# SCH_AGV_genzero_main_board_2024-06-24.net
KiCad netlist of a schematic drawn in EasyEDA
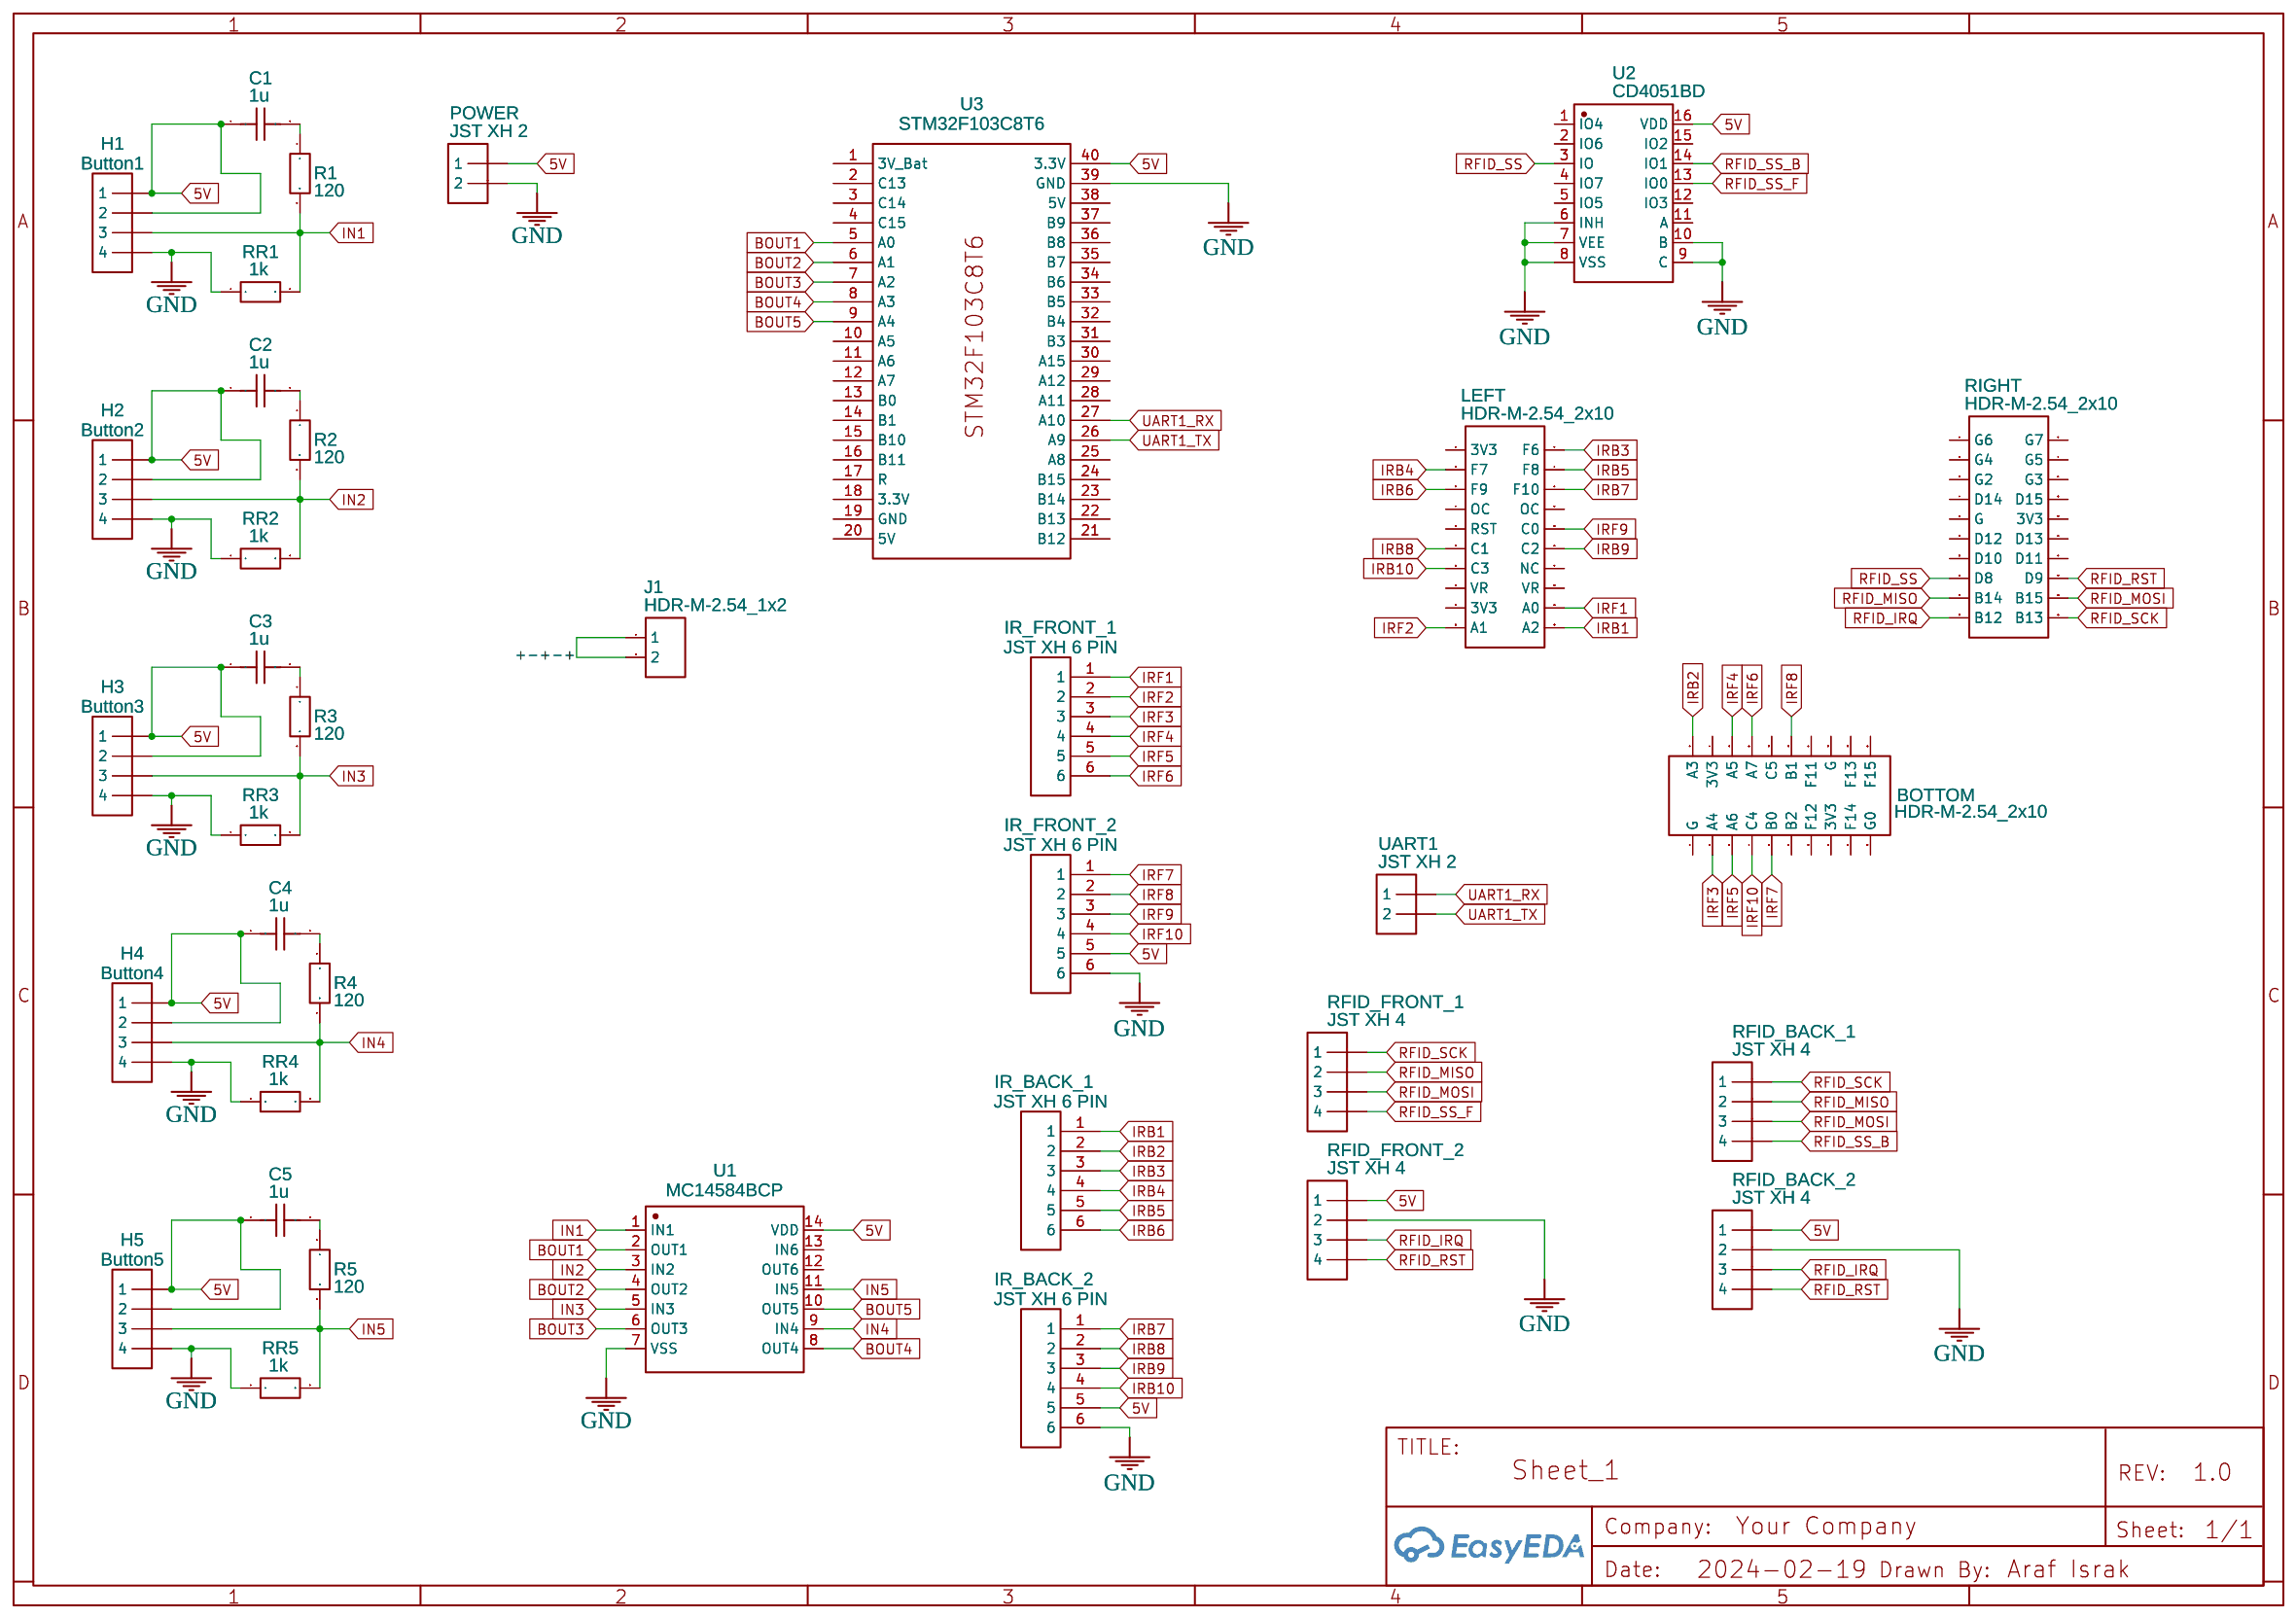
[diagram p0: schematic sheet]

(export (version "E")
  (design (tool "Eeschema 10.0.6"))
  (components
    (comp (ref "BOTTOM") (value "HDR-M-2.54_2x10") (libsource (lib "") (part "HDR-M-2.54_2x10_2")))
    (comp (ref "C1") (value "1u") (libsource (lib "") (part "C_RAD-0.1_US")))
    (comp (ref "C2") (value "1u") (libsource (lib "") (part "C_RAD-0.1_US")))
    (comp (ref "C3") (value "1u") (libsource (lib "") (part "C_RAD-0.1_US")))
    (comp (ref "C4") (value "1u") (libsource (lib "") (part "C_RAD-0.1_US")))
    (comp (ref "C5") (value "1u") (libsource (lib "") (part "C_RAD-0.1_US")))
    (comp (ref "H1") (value "Button1") (libsource (lib "") (part "JST XH 4_1")))
    (comp (ref "H2") (value "Button2") (libsource (lib "") (part "JST XH 4_1")))
    (comp (ref "H3") (value "Button3") (libsource (lib "") (part "JST XH 4_1")))
    (comp (ref "H4") (value "Button4") (libsource (lib "") (part "JST XH 4_1")))
    (comp (ref "H5") (value "Button5") (libsource (lib "") (part "JST XH 4_1")))
    (comp (ref "IR_BACK_1") (value "JST XH 6 PIN") (libsource (lib "") (part "JST XH 6 PIN")))
    (comp (ref "IR_BACK_2") (value "JST XH 6 PIN") (libsource (lib "") (part "JST XH 6 PIN")))
    (comp (ref "IR_FRONT_1") (value "JST XH 6 PIN") (libsource (lib "") (part "JST XH 6 PIN_1")))
    (comp (ref "IR_FRONT_2") (value "JST XH 6 PIN") (libsource (lib "") (part "JST XH 6 PIN_1")))
    (comp (ref "J1") (value "HDR-M-2.54_1x2") (libsource (lib "") (part "HDR-M-2.54_1x2")))
    (comp (ref "LEFT") (value "HDR-M-2.54_2x10") (libsource (lib "") (part "HDR-M-2.54_2x10")))
    (comp (ref "POWER") (value "JST XH 2") (libsource (lib "") (part "JST XH 2_1")))
    (comp (ref "R1") (value "120") (libsource (lib "") (part "R_AXIAL-0.4_EU_1")))
    (comp (ref "R2") (value "120") (libsource (lib "") (part "R_AXIAL-0.4_EU_1")))
    (comp (ref "R3") (value "120") (libsource (lib "") (part "R_AXIAL-0.4_EU_1")))
    (comp (ref "R4") (value "120") (libsource (lib "") (part "R_AXIAL-0.4_EU_1")))
    (comp (ref "R5") (value "120") (libsource (lib "") (part "R_AXIAL-0.4_EU_1")))
    (comp (ref "RFID_BACK_1") (value "JST XH 4") (libsource (lib "") (part "JST XH 4")))
    (comp (ref "RFID_BACK_2") (value "JST XH 4") (libsource (lib "") (part "JST XH 4")))
    (comp (ref "RFID_FRONT_1") (value "JST XH 4") (libsource (lib "") (part "JST XH 4_2")))
    (comp (ref "RFID_FRONT_2") (value "JST XH 4") (libsource (lib "") (part "JST XH 4_2")))
    (comp (ref "RIGHT") (value "HDR-M-2.54_2x10") (libsource (lib "") (part "HDR-M-2.54_2x10_1")))
    (comp (ref "RR1") (value "1k") (libsource (lib "") (part "R_AXIAL-0.4_EU")))
    (comp (ref "RR2") (value "1k") (libsource (lib "") (part "R_AXIAL-0.4_EU")))
    (comp (ref "RR3") (value "1k") (libsource (lib "") (part "R_AXIAL-0.4_EU")))
    (comp (ref "RR4") (value "1k") (libsource (lib "") (part "R_AXIAL-0.4_EU")))
    (comp (ref "RR5") (value "1k") (libsource (lib "") (part "R_AXIAL-0.4_EU")))
    (comp (ref "U1")
      (value "MC14584BCP")
      (fields (field (name "Manufacturer") "ON"))
      (libsource (lib "") (part "MC14584BCP"))
    )
    (comp (ref "U2")
      (value "CD4051BD")
      (fields (field (name "Manufacturer Part") "CD4051BF3A") (field (name "Manufacturer") "TI(德州仪器)"))
      (libsource (lib "") (part "CD4051BD"))
    )
    (comp (ref "U3") (value "STM32F103C8T6") (libsource (lib "") (part "STM32F103C8T6")))
    (comp (ref "UART1") (value "JST XH 2") (libsource (lib "") (part "JST XH 2")))
  )
  (nets
    (net (code "1") (name "/+-+-+") (class "Default")
      (node (ref "J1") (pin "1") (pinfunction "1_1") (pintype "unspecified"))
      (node (ref "J1") (pin "2") (pinfunction "2_2") (pintype "unspecified"))
    )
    (net (code "2") (name "5V") (class "Default")
      (node (ref "C1") (pin "1") (pinfunction "1_1") (pintype "unspecified"))
      (node (ref "C2") (pin "1") (pinfunction "1_1") (pintype "unspecified"))
      (node (ref "C3") (pin "1") (pinfunction "1_1") (pintype "unspecified"))
      (node (ref "C4") (pin "1") (pinfunction "1_1") (pintype "unspecified"))
      (node (ref "C5") (pin "1") (pinfunction "1_1") (pintype "unspecified"))
      (node (ref "H1") (pin "1") (pinfunction "1_1") (pintype "unspecified"))
      (node (ref "H1") (pin "2") (pinfunction "2_2") (pintype "unspecified"))
      (node (ref "H2") (pin "1") (pinfunction "1_1") (pintype "unspecified"))
      (node (ref "H2") (pin "2") (pinfunction "2_2") (pintype "unspecified"))
      (node (ref "H3") (pin "1") (pinfunction "1_1") (pintype "unspecified"))
      (node (ref "H3") (pin "2") (pinfunction "2_2") (pintype "unspecified"))
      (node (ref "H4") (pin "1") (pinfunction "1_1") (pintype "unspecified"))
      (node (ref "H4") (pin "2") (pinfunction "2_2") (pintype "unspecified"))
      (node (ref "H5") (pin "1") (pinfunction "1_1") (pintype "unspecified"))
      (node (ref "H5") (pin "2") (pinfunction "2_2") (pintype "unspecified"))
      (node (ref "IR_BACK_2") (pin "5") (pinfunction "5_5") (pintype "unspecified"))
      (node (ref "IR_FRONT_2") (pin "5") (pinfunction "5_5") (pintype "unspecified"))
      (node (ref "POWER") (pin "1") (pinfunction "1_1") (pintype "unspecified"))
      (node (ref "RFID_BACK_2") (pin "1") (pinfunction "1_1") (pintype "unspecified"))
      (node (ref "RFID_FRONT_2") (pin "1") (pinfunction "1_1") (pintype "unspecified"))
      (node (ref "U1") (pin "14") (pinfunction "VDD_14") (pintype "unspecified"))
      (node (ref "U2") (pin "16") (pinfunction "VDD_16") (pintype "unspecified"))
      (node (ref "U3") (pin "40") (pinfunction "3.3V_40") (pintype "unspecified"))
    )
    (net (code "3") (name "BOUT1") (class "Default")
      (node (ref "U1") (pin "2") (pinfunction "OUT1_2") (pintype "unspecified"))
      (node (ref "U3") (pin "5") (pinfunction "A0_5") (pintype "unspecified"))
    )
    (net (code "4") (name "BOUT2") (class "Default")
      (node (ref "U1") (pin "4") (pinfunction "OUT2_4") (pintype "unspecified"))
      (node (ref "U3") (pin "6") (pinfunction "A1_6") (pintype "unspecified"))
    )
    (net (code "5") (name "BOUT3") (class "Default")
      (node (ref "U1") (pin "6") (pinfunction "OUT3_6") (pintype "unspecified"))
      (node (ref "U3") (pin "7") (pinfunction "A2_7") (pintype "unspecified"))
    )
    (net (code "6") (name "BOUT4") (class "Default")
      (node (ref "U1") (pin "8") (pinfunction "OUT4_8") (pintype "unspecified"))
      (node (ref "U3") (pin "8") (pinfunction "A3_8") (pintype "unspecified"))
    )
    (net (code "7") (name "BOUT5") (class "Default")
      (node (ref "U1") (pin "10") (pinfunction "OUT5_10") (pintype "unspecified"))
      (node (ref "U3") (pin "9") (pinfunction "A4_9") (pintype "unspecified"))
    )
    (net (code "8") (name "GND") (class "Default")
      (node (ref "H1") (pin "4") (pinfunction "4_4") (pintype "unspecified"))
      (node (ref "H2") (pin "4") (pinfunction "4_4") (pintype "unspecified"))
      (node (ref "H3") (pin "4") (pinfunction "4_4") (pintype "unspecified"))
      (node (ref "H4") (pin "4") (pinfunction "4_4") (pintype "unspecified"))
      (node (ref "H5") (pin "4") (pinfunction "4_4") (pintype "unspecified"))
      (node (ref "IR_BACK_2") (pin "6") (pinfunction "6_6") (pintype "unspecified"))
      (node (ref "IR_FRONT_2") (pin "6") (pinfunction "6_6") (pintype "unspecified"))
      (node (ref "POWER") (pin "2") (pinfunction "2_2") (pintype "unspecified"))
      (node (ref "RFID_BACK_2") (pin "2") (pinfunction "2_2") (pintype "unspecified"))
      (node (ref "RFID_FRONT_2") (pin "2") (pinfunction "2_2") (pintype "unspecified"))
      (node (ref "RR1") (pin "1") (pinfunction "1_1") (pintype "unspecified"))
      (node (ref "RR2") (pin "1") (pinfunction "1_1") (pintype "unspecified"))
      (node (ref "RR3") (pin "1") (pinfunction "1_1") (pintype "unspecified"))
      (node (ref "RR4") (pin "1") (pinfunction "1_1") (pintype "unspecified"))
      (node (ref "RR5") (pin "1") (pinfunction "1_1") (pintype "unspecified"))
      (node (ref "U1") (pin "7") (pinfunction "VSS_7") (pintype "unspecified"))
      (node (ref "U2") (pin "10") (pinfunction "B_10") (pintype "unspecified"))
      (node (ref "U2") (pin "6") (pinfunction "INH_6") (pintype "unspecified"))
      (node (ref "U2") (pin "7") (pinfunction "VEE_7") (pintype "unspecified"))
      (node (ref "U2") (pin "8") (pinfunction "VSS_8") (pintype "unspecified"))
      (node (ref "U2") (pin "9") (pinfunction "C_9") (pintype "unspecified"))
      (node (ref "U3") (pin "39") (pinfunction "GND_39") (pintype "unspecified"))
    )
    (net (code "9") (name "IN1") (class "Default")
      (node (ref "H1") (pin "3") (pinfunction "3_3") (pintype "unspecified"))
      (node (ref "R1") (pin "2") (pinfunction "2_2") (pintype "unspecified"))
      (node (ref "RR1") (pin "2") (pinfunction "2_2") (pintype "unspecified"))
      (node (ref "U1") (pin "1") (pinfunction "IN1_1") (pintype "unspecified"))
    )
    (net (code "10") (name "IN2") (class "Default")
      (node (ref "H2") (pin "3") (pinfunction "3_3") (pintype "unspecified"))
      (node (ref "R2") (pin "2") (pinfunction "2_2") (pintype "unspecified"))
      (node (ref "RR2") (pin "2") (pinfunction "2_2") (pintype "unspecified"))
      (node (ref "U1") (pin "3") (pinfunction "IN2_3") (pintype "unspecified"))
    )
    (net (code "11") (name "IN3") (class "Default")
      (node (ref "H3") (pin "3") (pinfunction "3_3") (pintype "unspecified"))
      (node (ref "R3") (pin "2") (pinfunction "2_2") (pintype "unspecified"))
      (node (ref "RR3") (pin "2") (pinfunction "2_2") (pintype "unspecified"))
      (node (ref "U1") (pin "5") (pinfunction "IN3_5") (pintype "unspecified"))
    )
    (net (code "12") (name "IN4") (class "Default")
      (node (ref "H4") (pin "3") (pinfunction "3_3") (pintype "unspecified"))
      (node (ref "R4") (pin "2") (pinfunction "2_2") (pintype "unspecified"))
      (node (ref "RR4") (pin "2") (pinfunction "2_2") (pintype "unspecified"))
      (node (ref "U1") (pin "9") (pinfunction "IN4_9") (pintype "unspecified"))
    )
    (net (code "13") (name "IN5") (class "Default")
      (node (ref "H5") (pin "3") (pinfunction "3_3") (pintype "unspecified"))
      (node (ref "R5") (pin "2") (pinfunction "2_2") (pintype "unspecified"))
      (node (ref "RR5") (pin "2") (pinfunction "2_2") (pintype "unspecified"))
      (node (ref "U1") (pin "11") (pinfunction "IN5_11") (pintype "unspecified"))
    )
    (net (code "14") (name "IRB1") (class "Default")
      (node (ref "IR_BACK_1") (pin "1") (pinfunction "1_1") (pintype "unspecified"))
      (node (ref "LEFT") (pin "20") (pinfunction "A2_20") (pintype "unspecified"))
    )
    (net (code "15") (name "IRB2") (class "Default")
      (node (ref "BOTTOM") (pin "2") (pinfunction "A3_2") (pintype "unspecified"))
      (node (ref "IR_BACK_1") (pin "2") (pinfunction "2_2") (pintype "unspecified"))
    )
    (net (code "16") (name "IRB3") (class "Default")
      (node (ref "IR_BACK_1") (pin "3") (pinfunction "3_3") (pintype "unspecified"))
      (node (ref "LEFT") (pin "2") (pinfunction "F6_2") (pintype "unspecified"))
    )
    (net (code "17") (name "IRB4") (class "Default")
      (node (ref "IR_BACK_1") (pin "4") (pinfunction "4_4") (pintype "unspecified"))
      (node (ref "LEFT") (pin "3") (pinfunction "F7_3") (pintype "unspecified"))
    )
    (net (code "18") (name "IRB5") (class "Default")
      (node (ref "IR_BACK_1") (pin "5") (pinfunction "5_5") (pintype "unspecified"))
      (node (ref "LEFT") (pin "4") (pinfunction "F8_4") (pintype "unspecified"))
    )
    (net (code "19") (name "IRB6") (class "Default")
      (node (ref "IR_BACK_1") (pin "6") (pinfunction "6_6") (pintype "unspecified"))
      (node (ref "LEFT") (pin "5") (pinfunction "F9_5") (pintype "unspecified"))
    )
    (net (code "20") (name "IRB7") (class "Default")
      (node (ref "IR_BACK_2") (pin "1") (pinfunction "1_1") (pintype "unspecified"))
      (node (ref "LEFT") (pin "6") (pinfunction "F10_6") (pintype "unspecified"))
    )
    (net (code "21") (name "IRB8") (class "Default")
      (node (ref "IR_BACK_2") (pin "2") (pinfunction "2_2") (pintype "unspecified"))
      (node (ref "LEFT") (pin "11") (pinfunction "C1_11") (pintype "unspecified"))
    )
    (net (code "22") (name "IRB9") (class "Default")
      (node (ref "IR_BACK_2") (pin "3") (pinfunction "3_3") (pintype "unspecified"))
      (node (ref "LEFT") (pin "12") (pinfunction "C2_12") (pintype "unspecified"))
    )
    (net (code "23") (name "IRB10") (class "Default")
      (node (ref "IR_BACK_2") (pin "4") (pinfunction "4_4") (pintype "unspecified"))
      (node (ref "LEFT") (pin "13") (pinfunction "C3_13") (pintype "unspecified"))
    )
    (net (code "24") (name "IRF1") (class "Default")
      (node (ref "IR_FRONT_1") (pin "1") (pinfunction "1_1") (pintype "unspecified"))
      (node (ref "LEFT") (pin "18") (pinfunction "A0_18") (pintype "unspecified"))
    )
    (net (code "25") (name "IRF2") (class "Default")
      (node (ref "IR_FRONT_1") (pin "2") (pinfunction "2_2") (pintype "unspecified"))
      (node (ref "LEFT") (pin "19") (pinfunction "A1_19") (pintype "unspecified"))
    )
    (net (code "26") (name "IRF3") (class "Default")
      (node (ref "BOTTOM") (pin "3") (pinfunction "A4_3") (pintype "unspecified"))
      (node (ref "IR_FRONT_1") (pin "3") (pinfunction "3_3") (pintype "unspecified"))
    )
    (net (code "27") (name "IRF4") (class "Default")
      (node (ref "BOTTOM") (pin "6") (pinfunction "A5_6") (pintype "unspecified"))
      (node (ref "IR_FRONT_1") (pin "4") (pinfunction "4_4") (pintype "unspecified"))
    )
    (net (code "28") (name "IRF5") (class "Default")
      (node (ref "BOTTOM") (pin "5") (pinfunction "A6_5") (pintype "unspecified"))
      (node (ref "IR_FRONT_1") (pin "5") (pinfunction "5_5") (pintype "unspecified"))
    )
    (net (code "29") (name "IRF6") (class "Default")
      (node (ref "BOTTOM") (pin "8") (pinfunction "A7_8") (pintype "unspecified"))
      (node (ref "IR_FRONT_1") (pin "6") (pinfunction "6_6") (pintype "unspecified"))
    )
    (net (code "30") (name "IRF7") (class "Default")
      (node (ref "BOTTOM") (pin "9") (pinfunction "B0_9") (pintype "unspecified"))
      (node (ref "IR_FRONT_2") (pin "1") (pinfunction "1_1") (pintype "unspecified"))
    )
    (net (code "31") (name "IRF8") (class "Default")
      (node (ref "BOTTOM") (pin "12") (pinfunction "B1_12") (pintype "unspecified"))
      (node (ref "IR_FRONT_2") (pin "2") (pinfunction "2_2") (pintype "unspecified"))
    )
    (net (code "32") (name "IRF9") (class "Default")
      (node (ref "IR_FRONT_2") (pin "3") (pinfunction "3_3") (pintype "unspecified"))
      (node (ref "LEFT") (pin "10") (pinfunction "C0_10") (pintype "unspecified"))
    )
    (net (code "33") (name "IRF10") (class "Default")
      (node (ref "BOTTOM") (pin "7") (pinfunction "C4_7") (pintype "unspecified"))
      (node (ref "IR_FRONT_2") (pin "4") (pinfunction "4_4") (pintype "unspecified"))
    )
    (net (code "34") (name "Net-(C1-Pad2)") (class "Default")
      (node (ref "C1") (pin "2") (pinfunction "2_2") (pintype "unspecified"))
      (node (ref "R1") (pin "1") (pinfunction "1_1") (pintype "unspecified"))
    )
    (net (code "35") (name "Net-(C2-Pad2)") (class "Default")
      (node (ref "C2") (pin "2") (pinfunction "2_2") (pintype "unspecified"))
      (node (ref "R2") (pin "1") (pinfunction "1_1") (pintype "unspecified"))
    )
    (net (code "36") (name "Net-(C3-Pad2)") (class "Default")
      (node (ref "C3") (pin "2") (pinfunction "2_2") (pintype "unspecified"))
      (node (ref "R3") (pin "1") (pinfunction "1_1") (pintype "unspecified"))
    )
    (net (code "37") (name "Net-(C4-Pad2)") (class "Default")
      (node (ref "C4") (pin "2") (pinfunction "2_2") (pintype "unspecified"))
      (node (ref "R4") (pin "1") (pinfunction "1_1") (pintype "unspecified"))
    )
    (net (code "38") (name "Net-(C5-Pad2)") (class "Default")
      (node (ref "C5") (pin "2") (pinfunction "2_2") (pintype "unspecified"))
      (node (ref "R5") (pin "1") (pinfunction "1_1") (pintype "unspecified"))
    )
    (net (code "39") (name "RFID_IRQ") (class "Default")
      (node (ref "RFID_BACK_2") (pin "3") (pinfunction "3_3") (pintype "unspecified"))
      (node (ref "RFID_FRONT_2") (pin "3") (pinfunction "3_3") (pintype "unspecified"))
      (node (ref "RIGHT") (pin "19") (pinfunction "B12_19") (pintype "unspecified"))
    )
    (net (code "40") (name "RFID_MISO") (class "Default")
      (node (ref "RFID_BACK_1") (pin "2") (pinfunction "2_2") (pintype "unspecified"))
      (node (ref "RFID_FRONT_1") (pin "2") (pinfunction "2_2") (pintype "unspecified"))
      (node (ref "RIGHT") (pin "17") (pinfunction "B14_17") (pintype "unspecified"))
    )
    (net (code "41") (name "RFID_MOSI") (class "Default")
      (node (ref "RFID_BACK_1") (pin "3") (pinfunction "3_3") (pintype "unspecified"))
      (node (ref "RFID_FRONT_1") (pin "3") (pinfunction "3_3") (pintype "unspecified"))
      (node (ref "RIGHT") (pin "18") (pinfunction "B15_18") (pintype "unspecified"))
    )
    (net (code "42") (name "RFID_RST") (class "Default")
      (node (ref "RFID_BACK_2") (pin "4") (pinfunction "4_4") (pintype "unspecified"))
      (node (ref "RFID_FRONT_2") (pin "4") (pinfunction "4_4") (pintype "unspecified"))
      (node (ref "RIGHT") (pin "16") (pinfunction "D9_16") (pintype "unspecified"))
    )
    (net (code "43") (name "RFID_SCK") (class "Default")
      (node (ref "RFID_BACK_1") (pin "1") (pinfunction "1_1") (pintype "unspecified"))
      (node (ref "RFID_FRONT_1") (pin "1") (pinfunction "1_1") (pintype "unspecified"))
      (node (ref "RIGHT") (pin "20") (pinfunction "B13_20") (pintype "unspecified"))
    )
    (net (code "44") (name "RFID_SS") (class "Default")
      (node (ref "RIGHT") (pin "15") (pinfunction "D8_15") (pintype "unspecified"))
      (node (ref "U2") (pin "3") (pinfunction "IO_3") (pintype "unspecified"))
    )
    (net (code "45") (name "RFID_SS_B") (class "Default")
      (node (ref "RFID_BACK_1") (pin "4") (pinfunction "4_4") (pintype "unspecified"))
      (node (ref "U2") (pin "14") (pinfunction "IO1_14") (pintype "unspecified"))
    )
    (net (code "46") (name "RFID_SS_F") (class "Default")
      (node (ref "RFID_FRONT_1") (pin "4") (pinfunction "4_4") (pintype "unspecified"))
      (node (ref "U2") (pin "13") (pinfunction "IO0_13") (pintype "unspecified"))
    )
    (net (code "47") (name "UART1_RX") (class "Default")
      (node (ref "U3") (pin "27") (pinfunction "A10_27") (pintype "unspecified"))
      (node (ref "UART1") (pin "1") (pinfunction "1_1") (pintype "unspecified"))
    )
    (net (code "48") (name "UART1_TX") (class "Default")
      (node (ref "U3") (pin "26") (pinfunction "A9_26") (pintype "unspecified"))
      (node (ref "UART1") (pin "2") (pinfunction "2_2") (pintype "unspecified"))
    )
    (net (code "49") (name "unconnected-(BOTTOM-3V3-Pad4)") (class "Default")
      (node (ref "BOTTOM") (pin "4") (pinfunction "3V3_4") (pintype "unspecified"))
    )
    (net (code "50") (name "unconnected-(BOTTOM-3V3-Pad15)") (class "Default")
      (node (ref "BOTTOM") (pin "15") (pinfunction "3V3_15") (pintype "unspecified"))
    )
    (net (code "51") (name "unconnected-(BOTTOM-B2-Pad11)") (class "Default")
      (node (ref "BOTTOM") (pin "11") (pinfunction "B2_11") (pintype "unspecified"))
    )
    (net (code "52") (name "unconnected-(BOTTOM-C5-Pad10)") (class "Default")
      (node (ref "BOTTOM") (pin "10") (pinfunction "C5_10") (pintype "unspecified"))
    )
    (net (code "53") (name "unconnected-(BOTTOM-F11-Pad14)") (class "Default")
      (node (ref "BOTTOM") (pin "14") (pinfunction "F11_14") (pintype "unspecified"))
    )
    (net (code "54") (name "unconnected-(BOTTOM-F12-Pad13)") (class "Default")
      (node (ref "BOTTOM") (pin "13") (pinfunction "F12_13") (pintype "unspecified"))
    )
    (net (code "55") (name "unconnected-(BOTTOM-F13-Pad18)") (class "Default")
      (node (ref "BOTTOM") (pin "18") (pinfunction "F13_18") (pintype "unspecified"))
    )
    (net (code "56") (name "unconnected-(BOTTOM-F14-Pad17)") (class "Default")
      (node (ref "BOTTOM") (pin "17") (pinfunction "F14_17") (pintype "unspecified"))
    )
    (net (code "57") (name "unconnected-(BOTTOM-F15-Pad20)") (class "Default")
      (node (ref "BOTTOM") (pin "20") (pinfunction "F15_20") (pintype "unspecified"))
    )
    (net (code "58") (name "unconnected-(BOTTOM-G-Pad1)") (class "Default")
      (node (ref "BOTTOM") (pin "1") (pinfunction "G_1") (pintype "unspecified"))
    )
    (net (code "59") (name "unconnected-(BOTTOM-G-Pad16)") (class "Default")
      (node (ref "BOTTOM") (pin "16") (pinfunction "G_16") (pintype "unspecified"))
    )
    (net (code "60") (name "unconnected-(BOTTOM-G0-Pad19)") (class "Default")
      (node (ref "BOTTOM") (pin "19") (pinfunction "G0_19") (pintype "unspecified"))
    )
    (net (code "61") (name "unconnected-(LEFT-3V3-Pad1)") (class "Default")
      (node (ref "LEFT") (pin "1") (pinfunction "3V3_1") (pintype "unspecified"))
    )
    (net (code "62") (name "unconnected-(LEFT-3V3-Pad17)") (class "Default")
      (node (ref "LEFT") (pin "17") (pinfunction "3V3_17") (pintype "unspecified"))
    )
    (net (code "63") (name "unconnected-(LEFT-NC-Pad14)") (class "Default")
      (node (ref "LEFT") (pin "14") (pinfunction "NC_14") (pintype "unspecified"))
    )
    (net (code "64") (name "unconnected-(LEFT-OC-Pad7)") (class "Default")
      (node (ref "LEFT") (pin "7") (pinfunction "OC_7") (pintype "unspecified"))
    )
    (net (code "65") (name "unconnected-(LEFT-OC-Pad8)") (class "Default")
      (node (ref "LEFT") (pin "8") (pinfunction "OC_8") (pintype "unspecified"))
    )
    (net (code "66") (name "unconnected-(LEFT-RST-Pad9)") (class "Default")
      (node (ref "LEFT") (pin "9") (pinfunction "RST_9") (pintype "unspecified"))
    )
    (net (code "67") (name "unconnected-(LEFT-VR-Pad15)") (class "Default")
      (node (ref "LEFT") (pin "15") (pinfunction "VR_15") (pintype "unspecified"))
    )
    (net (code "68") (name "unconnected-(LEFT-VR-Pad16)") (class "Default")
      (node (ref "LEFT") (pin "16") (pinfunction "VR_16") (pintype "unspecified"))
    )
    (net (code "69") (name "unconnected-(RIGHT-3V3-Pad10)") (class "Default")
      (node (ref "RIGHT") (pin "10") (pinfunction "3V3_10") (pintype "unspecified"))
    )
    (net (code "70") (name "unconnected-(RIGHT-D10-Pad13)") (class "Default")
      (node (ref "RIGHT") (pin "13") (pinfunction "D10_13") (pintype "unspecified"))
    )
    (net (code "71") (name "unconnected-(RIGHT-D11-Pad14)") (class "Default")
      (node (ref "RIGHT") (pin "14") (pinfunction "D11_14") (pintype "unspecified"))
    )
    (net (code "72") (name "unconnected-(RIGHT-D12-Pad11)") (class "Default")
      (node (ref "RIGHT") (pin "11") (pinfunction "D12_11") (pintype "unspecified"))
    )
    (net (code "73") (name "unconnected-(RIGHT-D13-Pad12)") (class "Default")
      (node (ref "RIGHT") (pin "12") (pinfunction "D13_12") (pintype "unspecified"))
    )
    (net (code "74") (name "unconnected-(RIGHT-D14-Pad7)") (class "Default")
      (node (ref "RIGHT") (pin "7") (pinfunction "D14_7") (pintype "unspecified"))
    )
    (net (code "75") (name "unconnected-(RIGHT-D15-Pad8)") (class "Default")
      (node (ref "RIGHT") (pin "8") (pinfunction "D15_8") (pintype "unspecified"))
    )
    (net (code "76") (name "unconnected-(RIGHT-G-Pad9)") (class "Default")
      (node (ref "RIGHT") (pin "9") (pinfunction "G_9") (pintype "unspecified"))
    )
    (net (code "77") (name "unconnected-(RIGHT-G2-Pad5)") (class "Default")
      (node (ref "RIGHT") (pin "5") (pinfunction "G2_5") (pintype "unspecified"))
    )
    (net (code "78") (name "unconnected-(RIGHT-G3-Pad6)") (class "Default")
      (node (ref "RIGHT") (pin "6") (pinfunction "G3_6") (pintype "unspecified"))
    )
    (net (code "79") (name "unconnected-(RIGHT-G4-Pad3)") (class "Default")
      (node (ref "RIGHT") (pin "3") (pinfunction "G4_3") (pintype "unspecified"))
    )
    (net (code "80") (name "unconnected-(RIGHT-G5-Pad4)") (class "Default")
      (node (ref "RIGHT") (pin "4") (pinfunction "G5_4") (pintype "unspecified"))
    )
    (net (code "81") (name "unconnected-(RIGHT-G6-Pad1)") (class "Default")
      (node (ref "RIGHT") (pin "1") (pinfunction "G6_1") (pintype "unspecified"))
    )
    (net (code "82") (name "unconnected-(RIGHT-G7-Pad2)") (class "Default")
      (node (ref "RIGHT") (pin "2") (pinfunction "G7_2") (pintype "unspecified"))
    )
    (net (code "83") (name "unconnected-(U1-IN6-Pad13)") (class "Default")
      (node (ref "U1") (pin "13") (pinfunction "IN6_13") (pintype "unspecified"))
    )
    (net (code "84") (name "unconnected-(U1-OUT6-Pad12)") (class "Default")
      (node (ref "U1") (pin "12") (pinfunction "OUT6_12") (pintype "unspecified"))
    )
    (net (code "85") (name "unconnected-(U2-A-Pad11)") (class "Default")
      (node (ref "U2") (pin "11") (pinfunction "A_11") (pintype "unspecified"))
    )
    (net (code "86") (name "unconnected-(U2-IO2-Pad15)") (class "Default")
      (node (ref "U2") (pin "15") (pinfunction "IO2_15") (pintype "unspecified"))
    )
    (net (code "87") (name "unconnected-(U2-IO3-Pad12)") (class "Default")
      (node (ref "U2") (pin "12") (pinfunction "IO3_12") (pintype "unspecified"))
    )
    (net (code "88") (name "unconnected-(U2-IO4-Pad1)") (class "Default")
      (node (ref "U2") (pin "1") (pinfunction "IO4_1") (pintype "unspecified"))
    )
    (net (code "89") (name "unconnected-(U2-IO5-Pad5)") (class "Default")
      (node (ref "U2") (pin "5") (pinfunction "IO5_5") (pintype "unspecified"))
    )
    (net (code "90") (name "unconnected-(U2-IO6-Pad2)") (class "Default")
      (node (ref "U2") (pin "2") (pinfunction "IO6_2") (pintype "unspecified"))
    )
    (net (code "91") (name "unconnected-(U2-IO7-Pad4)") (class "Default")
      (node (ref "U2") (pin "4") (pinfunction "IO7_4") (pintype "unspecified"))
    )
    (net (code "92") (name "unconnected-(U3-3.3V-Pad18)") (class "Default")
      (node (ref "U3") (pin "18") (pinfunction "3.3V_18") (pintype "unspecified"))
    )
    (net (code "93") (name "unconnected-(U3-3V_Bat-Pad1)") (class "Default")
      (node (ref "U3") (pin "1") (pinfunction "3V_Bat_1") (pintype "unspecified"))
    )
    (net (code "94") (name "unconnected-(U3-5V-Pad20)") (class "Default")
      (node (ref "U3") (pin "20") (pinfunction "5V_20") (pintype "unspecified"))
    )
    (net (code "95") (name "unconnected-(U3-5V-Pad38)") (class "Default")
      (node (ref "U3") (pin "38") (pinfunction "5V_38") (pintype "unspecified"))
    )
    (net (code "96") (name "unconnected-(U3-A5-Pad10)") (class "Default")
      (node (ref "U3") (pin "10") (pinfunction "A5_10") (pintype "unspecified"))
    )
    (net (code "97") (name "unconnected-(U3-A6-Pad11)") (class "Default")
      (node (ref "U3") (pin "11") (pinfunction "A6_11") (pintype "unspecified"))
    )
    (net (code "98") (name "unconnected-(U3-A7-Pad12)") (class "Default")
      (node (ref "U3") (pin "12") (pinfunction "A7_12") (pintype "unspecified"))
    )
    (net (code "99") (name "unconnected-(U3-A8-Pad25)") (class "Default")
      (node (ref "U3") (pin "25") (pinfunction "A8_25") (pintype "unspecified"))
    )
    (net (code "100") (name "unconnected-(U3-A11-Pad28)") (class "Default")
      (node (ref "U3") (pin "28") (pinfunction "A11_28") (pintype "unspecified"))
    )
    (net (code "101") (name "unconnected-(U3-A12-Pad29)") (class "Default")
      (node (ref "U3") (pin "29") (pinfunction "A12_29") (pintype "unspecified"))
    )
    (net (code "102") (name "unconnected-(U3-A15-Pad30)") (class "Default")
      (node (ref "U3") (pin "30") (pinfunction "A15_30") (pintype "unspecified"))
    )
    (net (code "103") (name "unconnected-(U3-B0-Pad13)") (class "Default")
      (node (ref "U3") (pin "13") (pinfunction "B0_13") (pintype "unspecified"))
    )
    (net (code "104") (name "unconnected-(U3-B1-Pad14)") (class "Default")
      (node (ref "U3") (pin "14") (pinfunction "B1_14") (pintype "unspecified"))
    )
    (net (code "105") (name "unconnected-(U3-B3-Pad31)") (class "Default")
      (node (ref "U3") (pin "31") (pinfunction "B3_31") (pintype "unspecified"))
    )
    (net (code "106") (name "unconnected-(U3-B4-Pad32)") (class "Default")
      (node (ref "U3") (pin "32") (pinfunction "B4_32") (pintype "unspecified"))
    )
    (net (code "107") (name "unconnected-(U3-B5-Pad33)") (class "Default")
      (node (ref "U3") (pin "33") (pinfunction "B5_33") (pintype "unspecified"))
    )
    (net (code "108") (name "unconnected-(U3-B6-Pad34)") (class "Default")
      (node (ref "U3") (pin "34") (pinfunction "B6_34") (pintype "unspecified"))
    )
    (net (code "109") (name "unconnected-(U3-B7-Pad35)") (class "Default")
      (node (ref "U3") (pin "35") (pinfunction "B7_35") (pintype "unspecified"))
    )
    (net (code "110") (name "unconnected-(U3-B8-Pad36)") (class "Default")
      (node (ref "U3") (pin "36") (pinfunction "B8_36") (pintype "unspecified"))
    )
    (net (code "111") (name "unconnected-(U3-B9-Pad37)") (class "Default")
      (node (ref "U3") (pin "37") (pinfunction "B9_37") (pintype "unspecified"))
    )
    (net (code "112") (name "unconnected-(U3-B10-Pad15)") (class "Default")
      (node (ref "U3") (pin "15") (pinfunction "B10_15") (pintype "unspecified"))
    )
    (net (code "113") (name "unconnected-(U3-B11-Pad16)") (class "Default")
      (node (ref "U3") (pin "16") (pinfunction "B11_16") (pintype "unspecified"))
    )
    (net (code "114") (name "unconnected-(U3-B12-Pad21)") (class "Default")
      (node (ref "U3") (pin "21") (pinfunction "B12_21") (pintype "bidirectional"))
    )
    (net (code "115") (name "unconnected-(U3-B13-Pad22)") (class "Default")
      (node (ref "U3") (pin "22") (pinfunction "B13_22") (pintype "bidirectional"))
    )
    (net (code "116") (name "unconnected-(U3-B14-Pad23)") (class "Default")
      (node (ref "U3") (pin "23") (pinfunction "B14_23") (pintype "bidirectional"))
    )
    (net (code "117") (name "unconnected-(U3-B15-Pad24)") (class "Default")
      (node (ref "U3") (pin "24") (pinfunction "B15_24") (pintype "bidirectional"))
    )
    (net (code "118") (name "unconnected-(U3-C13-Pad2)") (class "Default")
      (node (ref "U3") (pin "2") (pinfunction "C13_2") (pintype "unspecified"))
    )
    (net (code "119") (name "unconnected-(U3-C14-Pad3)") (class "Default")
      (node (ref "U3") (pin "3") (pinfunction "C14_3") (pintype "unspecified"))
    )
    (net (code "120") (name "unconnected-(U3-C15-Pad4)") (class "Default")
      (node (ref "U3") (pin "4") (pinfunction "C15_4") (pintype "unspecified"))
    )
    (net (code "121") (name "unconnected-(U3-GND-Pad19)") (class "Default")
      (node (ref "U3") (pin "19") (pinfunction "GND_19") (pintype "unspecified"))
    )
    (net (code "122") (name "unconnected-(U3-R-Pad17)") (class "Default")
      (node (ref "U3") (pin "17") (pinfunction "R_17") (pintype "unspecified"))
    )
  )
)
